# switches.net
KiCad netlist of a schematic drawn in Altium Designer
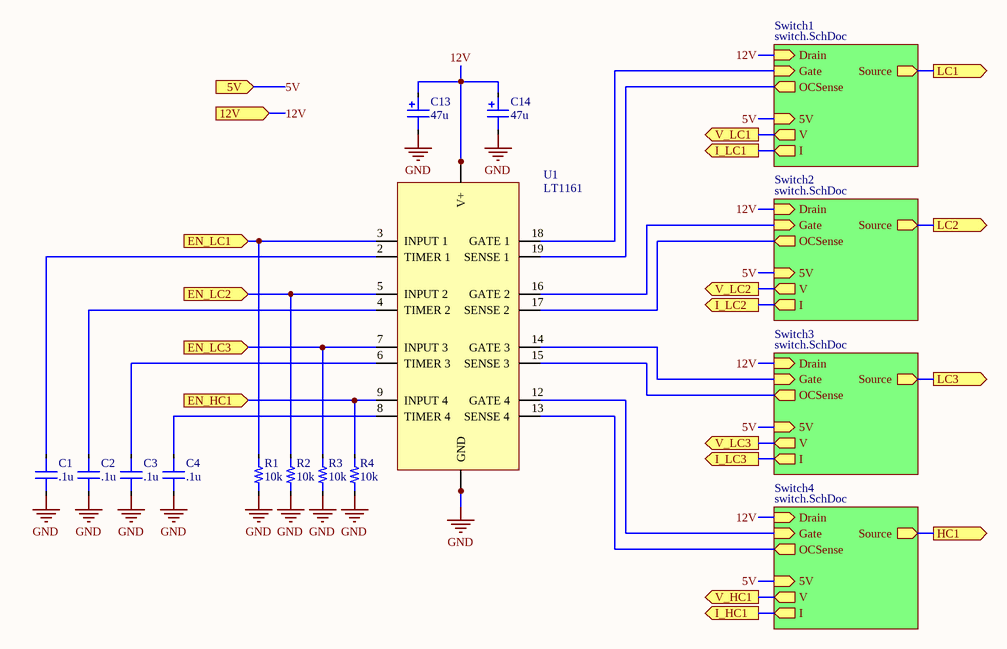
[diagram p0: switches.SchDoc]

(export (version "E")
  (design (tool "Eeschema 10.0.6"))
  (components
    (comp (ref "C1")
      (value ".1u")
      (footprint "0603_CAP")
      (fields (field (name "Comment") "Capacitor"))
      (libsource (lib "Capacitors") (part "Capacitor"))
    )
    (comp (ref "C2")
      (value ".1u")
      (footprint "0603_CAP")
      (fields (field (name "Comment") "Capacitor"))
      (libsource (lib "Capacitors") (part "Capacitor"))
    )
    (comp (ref "C3")
      (value ".1u")
      (footprint "0603_CAP")
      (fields (field (name "Comment") "Capacitor"))
      (libsource (lib "Capacitors") (part "Capacitor"))
    )
    (comp (ref "C4")
      (value ".1u")
      (footprint "0603_CAP")
      (fields (field (name "Comment") "Capacitor"))
      (libsource (lib "Capacitors") (part "Capacitor"))
    )
    (comp (ref "C13")
      (value "47u")
      (footprint "CAPAE6666X77M")
      (description "CAP ALUM 47UF 20% 50V SMD")
      (fields (field (name "Comment") "UWT1H470MCL1GS"))
      (libsource (lib "Capacitors") (part "UWT1H470MCL1GS"))
    )
    (comp (ref "C14")
      (value "47u")
      (footprint "CAPAE6666X77M")
      (description "CAP ALUM 47UF 20% 50V SMD")
      (fields (field (name "Comment") "UWT1H470MCL1GS"))
      (libsource (lib "Capacitors") (part "UWT1H470MCL1GS"))
    )
    (comp (ref "R1")
      (value "10k")
      (footprint "0603_RES")
      (fields (field (name "Comment") "Resistor"))
      (libsource (lib "Resistors") (part "Resistor"))
    )
    (comp (ref "R2")
      (value "10k")
      (footprint "0603_RES")
      (fields (field (name "Comment") "Resistor"))
      (libsource (lib "Resistors") (part "Resistor"))
    )
    (comp (ref "R3")
      (value "10k")
      (footprint "0603_RES")
      (fields (field (name "Comment") "Resistor"))
      (libsource (lib "Resistors") (part "Resistor"))
    )
    (comp (ref "R4")
      (value "10k")
      (footprint "0603_RES")
      (fields (field (name "Comment") "Resistor"))
      (libsource (lib "Resistors") (part "Resistor"))
    )
    (comp (ref "U1") (value "LT1161") (footprint "SO-20") (libsource (lib "Power") (part "LT1161")))
  )
  (nets
    (net (code "2") (name "/12V") (class "Default")
      (node (ref "C13") (pin "1") (pinfunction "1_1") (pintype "passive"))
      (node (ref "C14") (pin "1") (pinfunction "1_1") (pintype "passive"))
      (node (ref "U1") (pin "11") (pinfunction "V+_11") (pintype "passive"))
      (node (ref "U1") (pin "20") (pinfunction "V+_20") (pintype "passive"))
    )
    (net (code "3") (name "/EN_HC1") (class "Default")
      (node (ref "R4") (pin "2") (pinfunction "2_2") (pintype "passive"))
      (node (ref "U1") (pin "9") (pinfunction "INPUT_4_9") (pintype "passive"))
    )
    (net (code "4") (name "/EN_LC1") (class "Default")
      (node (ref "R1") (pin "2") (pinfunction "2_2") (pintype "passive"))
      (node (ref "U1") (pin "3") (pinfunction "INPUT_1_3") (pintype "passive"))
    )
    (net (code "5") (name "/EN_LC2") (class "Default")
      (node (ref "R2") (pin "2") (pinfunction "2_2") (pintype "passive"))
      (node (ref "U1") (pin "5") (pinfunction "INPUT_2_5") (pintype "passive"))
    )
    (net (code "6") (name "/EN_LC3") (class "Default")
      (node (ref "R3") (pin "2") (pinfunction "2_2") (pintype "passive"))
      (node (ref "U1") (pin "7") (pinfunction "INPUT_3_7") (pintype "passive"))
    )
    (net (code "7") (name "/Gate") (class "Default")
      (node (ref "U1") (pin "18") (pinfunction "GATE_1_18") (pintype "passive"))
    )
    (net (code "8") (name "/Gate_1") (class "Default")
      (node (ref "U1") (pin "16") (pinfunction "GATE_2_16") (pintype "passive"))
    )
    (net (code "9") (name "/Gate_2") (class "Default")
      (node (ref "U1") (pin "14") (pinfunction "GATE_3_14") (pintype "passive"))
    )
    (net (code "10") (name "/Gate_3") (class "Default")
      (node (ref "U1") (pin "12") (pinfunction "GATE_4_12") (pintype "passive"))
    )
    (net (code "19") (name "/OCSense") (class "Default")
      (node (ref "U1") (pin "19") (pinfunction "SENSE_1_19") (pintype "passive"))
    )
    (net (code "20") (name "/OCSense_1") (class "Default")
      (node (ref "U1") (pin "17") (pinfunction "SENSE_2_17") (pintype "passive"))
    )
    (net (code "21") (name "/OCSense_2") (class "Default")
      (node (ref "U1") (pin "15") (pinfunction "SENSE_3_15") (pintype "passive"))
    )
    (net (code "22") (name "/OCSense_3") (class "Default")
      (node (ref "U1") (pin "13") (pinfunction "SENSE_4_13") (pintype "passive"))
    )
    (net (code "27") (name "GND") (class "Default")
      (node (ref "C1") (pin "1") (pinfunction "1_1") (pintype "passive"))
      (node (ref "C13") (pin "2") (pinfunction "2_2") (pintype "passive"))
      (node (ref "C14") (pin "2") (pinfunction "2_2") (pintype "passive"))
      (node (ref "C2") (pin "1") (pinfunction "1_1") (pintype "passive"))
      (node (ref "C3") (pin "1") (pinfunction "1_1") (pintype "passive"))
      (node (ref "C4") (pin "1") (pinfunction "1_1") (pintype "passive"))
      (node (ref "R1") (pin "1") (pinfunction "1_1") (pintype "passive"))
      (node (ref "R2") (pin "1") (pinfunction "1_1") (pintype "passive"))
      (node (ref "R3") (pin "1") (pinfunction "1_1") (pintype "passive"))
      (node (ref "R4") (pin "1") (pinfunction "1_1") (pintype "passive"))
      (node (ref "U1") (pin "1") (pinfunction "GND_1") (pintype "passive"))
      (node (ref "U1") (pin "10") (pinfunction "GND_10") (pintype "passive"))
    )
    (net (code "28") (name "Net-(U1-TIMER_1)") (class "Default")
      (node (ref "C1") (pin "2") (pinfunction "2_2") (pintype "passive"))
      (node (ref "U1") (pin "2") (pinfunction "TIMER_1_2") (pintype "passive"))
    )
    (net (code "29") (name "Net-(U1-TIMER_2)") (class "Default")
      (node (ref "C2") (pin "2") (pinfunction "2_2") (pintype "passive"))
      (node (ref "U1") (pin "4") (pinfunction "TIMER_2_4") (pintype "passive"))
    )
    (net (code "30") (name "Net-(U1-TIMER_3)") (class "Default")
      (node (ref "C3") (pin "2") (pinfunction "2_2") (pintype "passive"))
      (node (ref "U1") (pin "6") (pinfunction "TIMER_3_6") (pintype "passive"))
    )
    (net (code "31") (name "Net-(U1-TIMER_4)") (class "Default")
      (node (ref "C4") (pin "2") (pinfunction "2_2") (pintype "passive"))
      (node (ref "U1") (pin "8") (pinfunction "TIMER_4_8") (pintype "passive"))
    )
  )
)
